# esp8266-dev-board.net
KiCad netlist of a schematic drawn in EAGLE
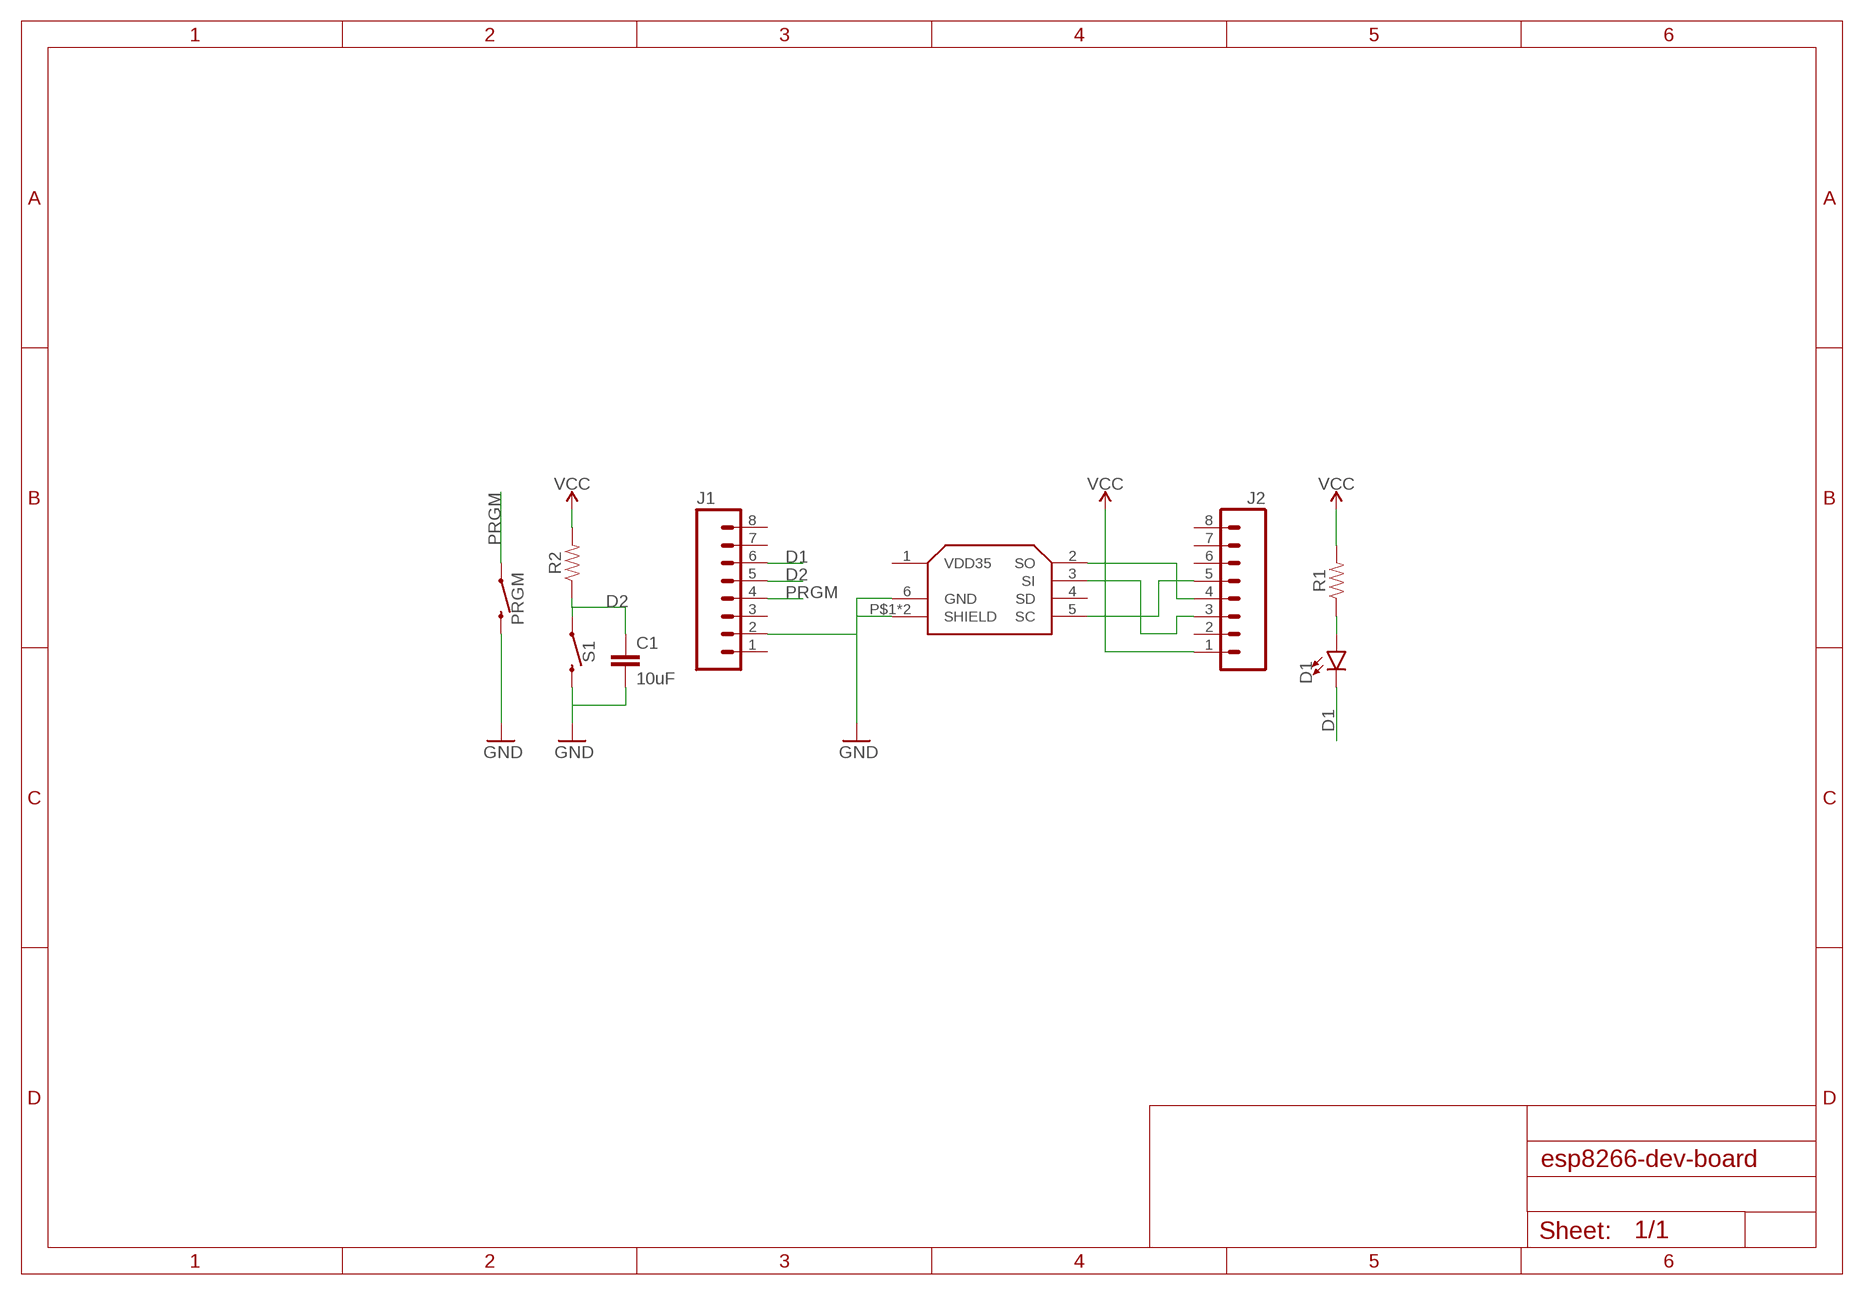
[diagram p0: schematic, sheet 1]

(export (version "E")
  (design (tool "Eeschema 10.0.6"))
  (components
    (comp (ref "C1")
      (value "10uF")
      (footprint "eagle-import:0805")
      (libsource (lib "eagle-import") (part "10UF-0805-10V-10%"))
    )
    (comp (ref "D1")
      (value "LED0603")
      (footprint "eagle-import:LED-0603")
      (libsource (lib "eagle-import") (part "LED0603"))
    )
    (comp (ref "J1")
      (value "M08")
      (footprint "eagle-import:1X08_ROUND")
      (libsource (lib "eagle-import") (part "M08"))
    )
    (comp (ref "J2")
      (value "M08")
      (footprint "eagle-import:1X08_ROUND")
      (libsource (lib "eagle-import") (part "M08"))
    )
    (comp (ref "PRGM")
      (value "MOMENTARY-SWITCH-SPST-SMD-6.0X3.5MM")
      (footprint "eagle-import:TACTILE_SWITCH_SMD_6.0X3.5MM")
      (libsource (lib "eagle-import") (part "MOMENTARY-SWITCH-SPST-SMD-6.0X3.5MM"))
    )
    (comp (ref "R1")
      (value "RESISTOR0805")
      (footprint "eagle-import:0805")
      (libsource (lib "eagle-import") (part "RESISTOR0805"))
    )
    (comp (ref "R2")
      (value "RESISTOR0805")
      (footprint "eagle-import:0805")
      (libsource (lib "eagle-import") (part "RESISTOR0805"))
    )
    (comp (ref "S1")
      (value "MOMENTARY-SWITCH-SPST-SMD-6.0X3.5MM")
      (footprint "eagle-import:TACTILE_SWITCH_SMD_6.0X3.5MM")
      (libsource (lib "eagle-import") (part "MOMENTARY-SWITCH-SPST-SMD-6.0X3.5MM"))
    )
    (comp (ref "U$1")
      (value "EXT-PORT-AGB")
      (footprint "eagle-import:EXT-PORT-AGB")
      (libsource (lib "eagle-import") (part "EXT-PORT-AGB"))
    )
  )
  (nets
    (net (code "1") (name "/D1") (class "Default")
      (node (ref "D1") (pin "C") (pinfunction "C_C") (pintype "passive"))
      (node (ref "J1") (pin "6") (pinfunction "6_6") (pintype "passive"))
    )
    (net (code "2") (name "/D2") (class "Default")
      (node (ref "C1") (pin "1") (pinfunction "1_1") (pintype "passive"))
      (node (ref "J1") (pin "5") (pinfunction "5_5") (pintype "passive"))
      (node (ref "R2") (pin "1") (pinfunction "1_1") (pintype "passive"))
      (node (ref "S1") (pin "1") (pinfunction "1_1") (pintype "passive"))
    )
    (net (code "3") (name "/PRGM") (class "Default")
      (node (ref "J1") (pin "4") (pinfunction "4_4") (pintype "passive"))
      (node (ref "PRGM") (pin "1") (pinfunction "1_1") (pintype "passive"))
    )
    (net (code "4") (name "GND") (class "Default")
      (node (ref "C1") (pin "2") (pinfunction "2_2") (pintype "passive"))
      (node (ref "J1") (pin "2") (pinfunction "2_2") (pintype "passive"))
      (node (ref "PRGM") (pin "2") (pinfunction "2_2") (pintype "passive"))
      (node (ref "S1") (pin "2") (pinfunction "2_2") (pintype "passive"))
      (node (ref "U$1") (pin "6") (pinfunction "GND_6") (pintype "bidirectional"))
      (node (ref "U$1") (pin "P$1") (pinfunction "SHIELD_P$1") (pintype "bidirectional"))
      (node (ref "U$1") (pin "P$2") (pinfunction "SHIELD_P$2") (pintype "bidirectional"))
    )
    (net (code "5") (name "Net-(D1-PadA)") (class "Default")
      (node (ref "D1") (pin "A") (pinfunction "A_A") (pintype "passive"))
      (node (ref "R1") (pin "1") (pinfunction "1_1") (pintype "passive"))
    )
    (net (code "6") (name "Net-(U$1-SC)") (class "Default")
      (node (ref "J2") (pin "5") (pinfunction "5_5") (pintype "passive"))
      (node (ref "U$1") (pin "5") (pinfunction "SC_5") (pintype "bidirectional"))
    )
    (net (code "7") (name "Net-(U$1-SI)") (class "Default")
      (node (ref "J2") (pin "3") (pinfunction "3_3") (pintype "passive"))
      (node (ref "U$1") (pin "3") (pinfunction "SI_3") (pintype "bidirectional"))
    )
    (net (code "8") (name "Net-(U$1-SO)") (class "Default")
      (node (ref "J2") (pin "4") (pinfunction "4_4") (pintype "passive"))
      (node (ref "U$1") (pin "2") (pinfunction "SO_2") (pintype "bidirectional"))
    )
    (net (code "9") (name "VCC") (class "Default")
      (node (ref "J2") (pin "1") (pinfunction "1_1") (pintype "passive"))
      (node (ref "R1") (pin "2") (pinfunction "2_2") (pintype "passive"))
      (node (ref "R2") (pin "2") (pinfunction "2_2") (pintype "passive"))
    )
    (net (code "10") (name "unconnected-(J1-Pad1)") (class "Default")
      (node (ref "J1") (pin "1") (pinfunction "1_1") (pintype "passive"))
    )
    (net (code "11") (name "unconnected-(J1-Pad3)") (class "Default")
      (node (ref "J1") (pin "3") (pinfunction "3_3") (pintype "passive"))
    )
    (net (code "12") (name "unconnected-(J1-Pad7)") (class "Default")
      (node (ref "J1") (pin "7") (pinfunction "7_7") (pintype "passive"))
    )
    (net (code "13") (name "unconnected-(J1-Pad8)") (class "Default")
      (node (ref "J1") (pin "8") (pinfunction "8_8") (pintype "passive"))
    )
    (net (code "14") (name "unconnected-(J2-Pad2)") (class "Default")
      (node (ref "J2") (pin "2") (pinfunction "2_2") (pintype "passive"))
    )
    (net (code "15") (name "unconnected-(J2-Pad6)") (class "Default")
      (node (ref "J2") (pin "6") (pinfunction "6_6") (pintype "passive"))
    )
    (net (code "16") (name "unconnected-(J2-Pad7)") (class "Default")
      (node (ref "J2") (pin "7") (pinfunction "7_7") (pintype "passive"))
    )
    (net (code "17") (name "unconnected-(J2-Pad8)") (class "Default")
      (node (ref "J2") (pin "8") (pinfunction "8_8") (pintype "passive"))
    )
    (net (code "18") (name "unconnected-(U$1-SD-Pad4)") (class "Default")
      (node (ref "U$1") (pin "4") (pinfunction "SD_4") (pintype "bidirectional"))
    )
    (net (code "19") (name "unconnected-(U$1-VDD35-Pad1)") (class "Default")
      (node (ref "U$1") (pin "1") (pinfunction "VDD35_1") (pintype "bidirectional"))
    )
  )
)
